# MAPE-CUN-Large-033.net
KiCad netlist of a schematic drawn in EAGLE
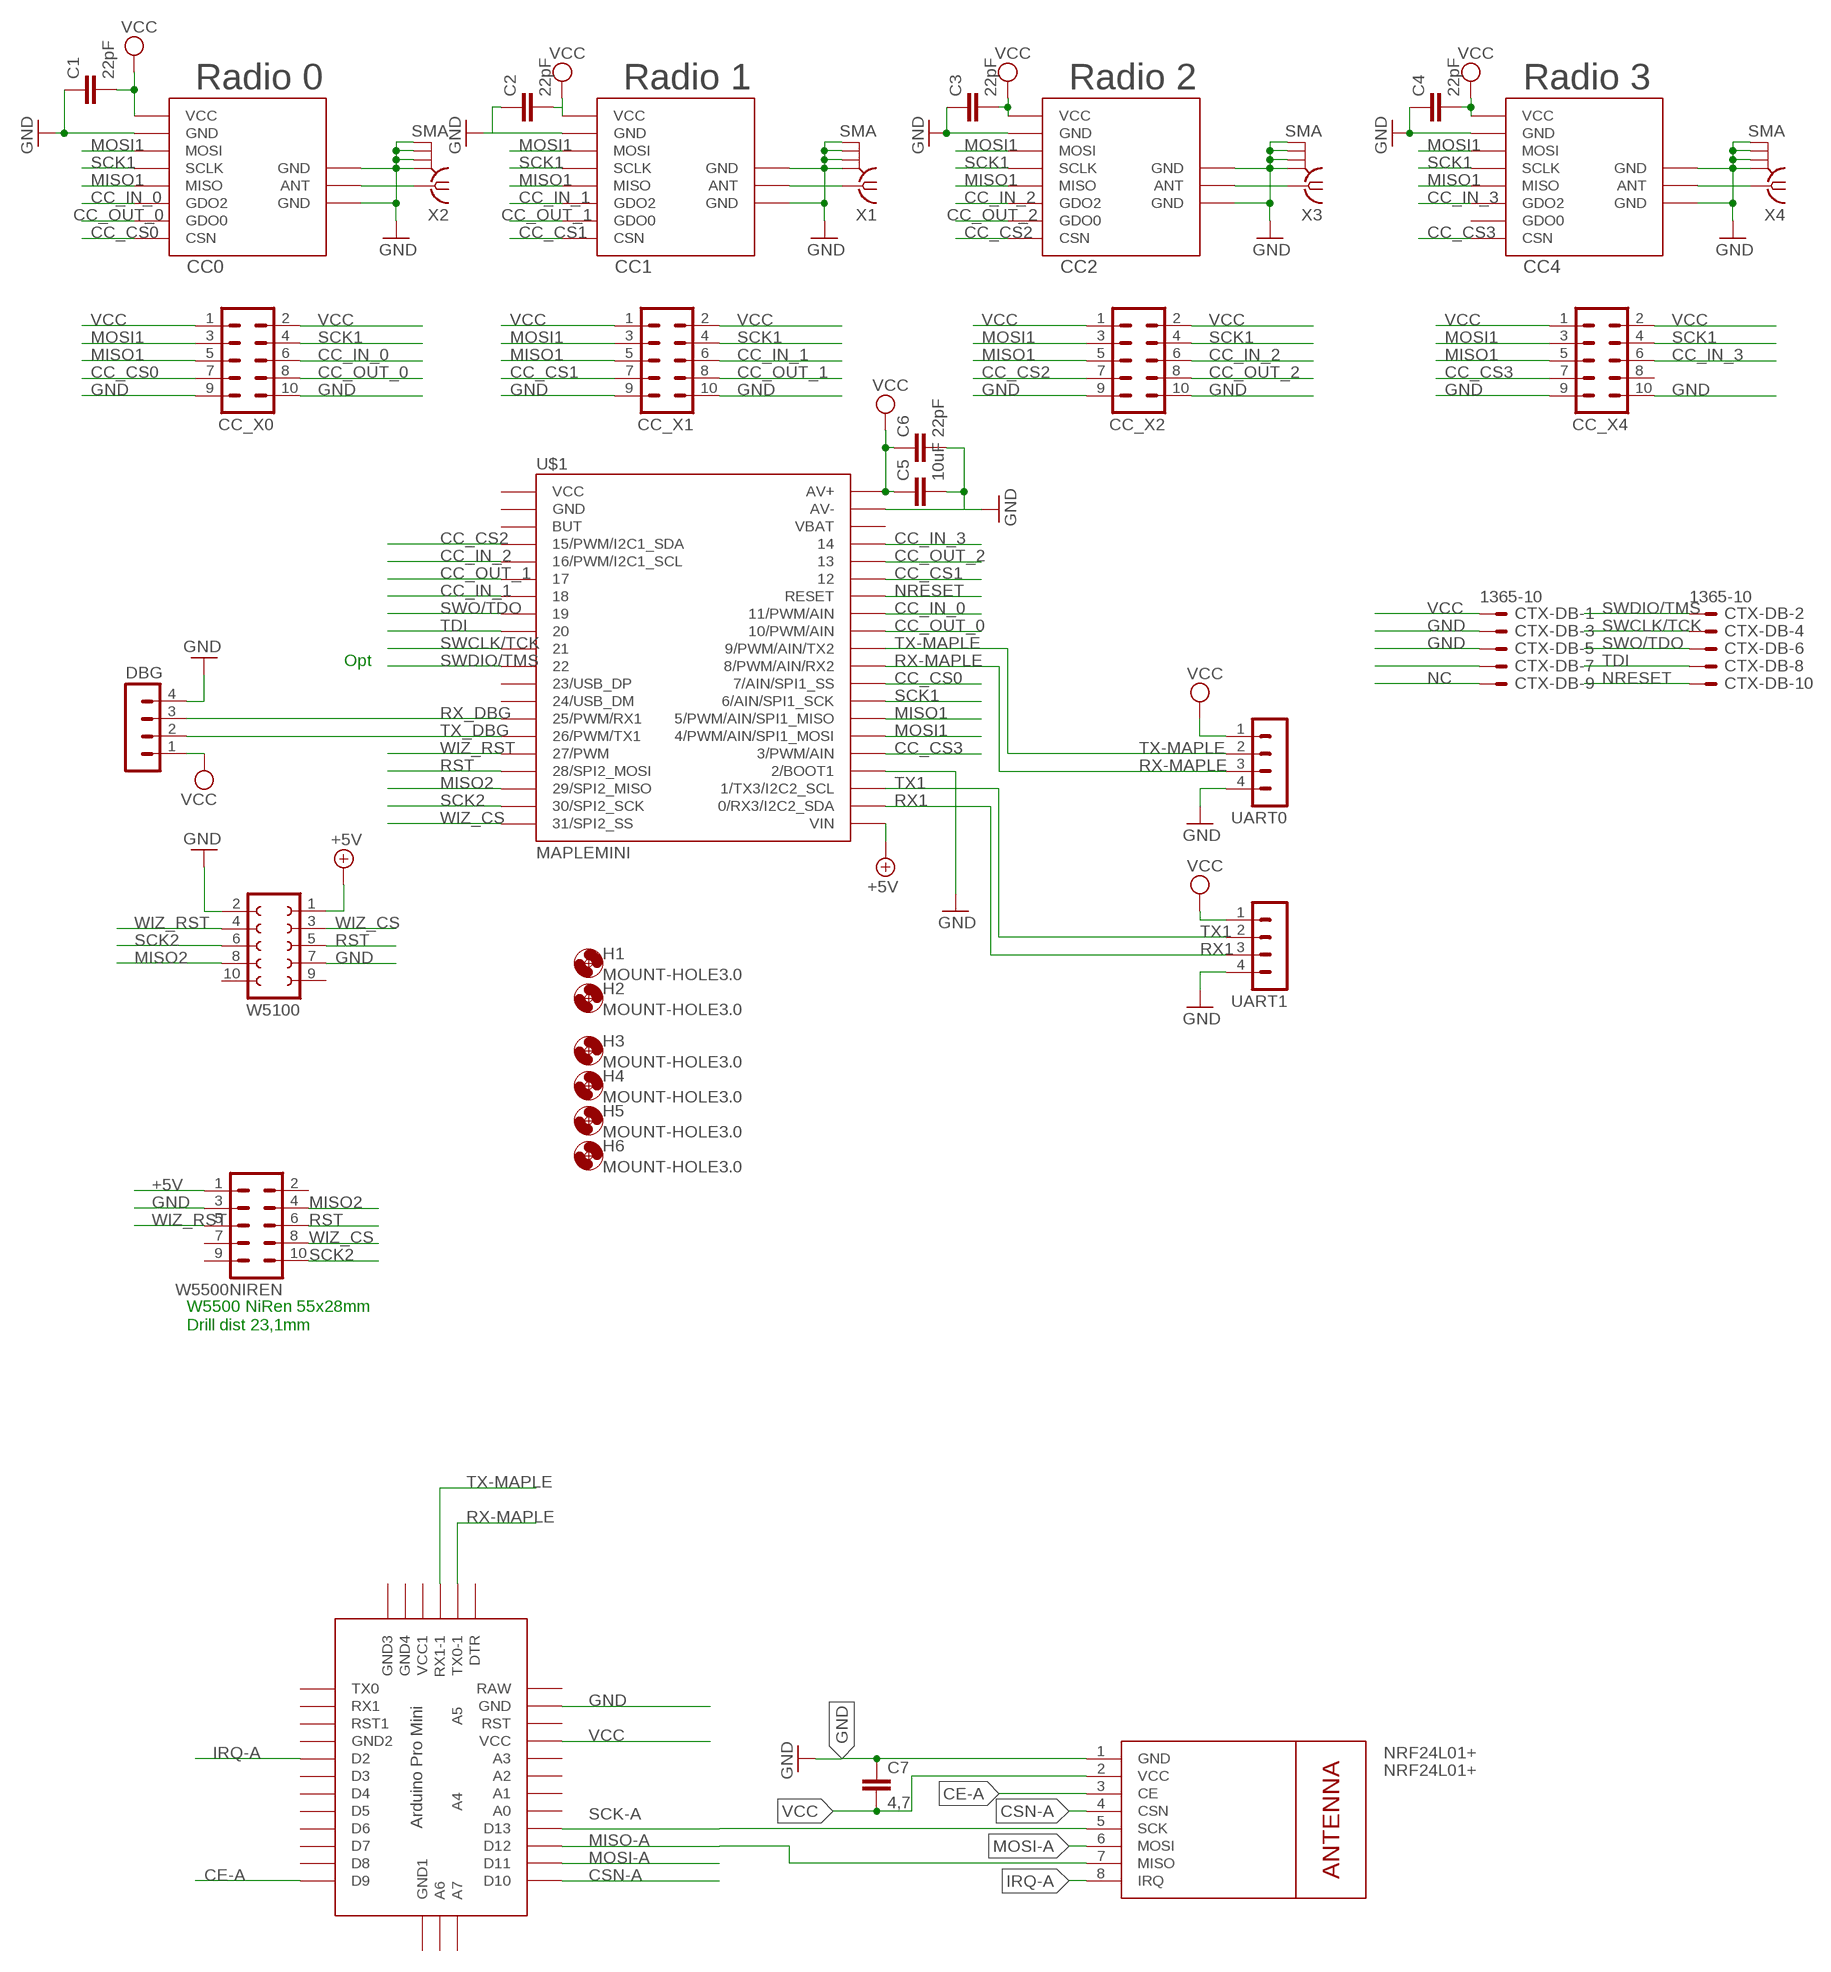
[diagram p0: schematic, sheet 1]

(export (version "E")
  (design (tool "Eeschema 10.0.6"))
  (components
    (comp (ref "C1")
      (value "22pF")
      (footprint "eagle-import:C0805")
      (libsource (lib "eagle-import") (part "C-EUC0805"))
    )
    (comp (ref "C2")
      (value "22pF")
      (footprint "eagle-import:C0805")
      (libsource (lib "eagle-import") (part "C-EUC0805"))
    )
    (comp (ref "C3")
      (value "22pF")
      (footprint "eagle-import:C0805")
      (libsource (lib "eagle-import") (part "C-EUC0805"))
    )
    (comp (ref "C4")
      (value "22pF")
      (footprint "eagle-import:C0805")
      (libsource (lib "eagle-import") (part "C-EUC0805"))
    )
    (comp (ref "C5")
      (value "10uF")
      (footprint "eagle-import:C1210")
      (libsource (lib "eagle-import") (part "C-EUC1210"))
    )
    (comp (ref "C6")
      (value "22pF")
      (footprint "eagle-import:C0805")
      (libsource (lib "eagle-import") (part "C-EUC0805"))
    )
    (comp (ref "C7")
      (value "4,7")
      (footprint "eagle-import:C1210")
      (libsource (lib "eagle-import") (part "C-EUC1210"))
    )
    (comp (ref "CC0")
      (value "CC1101_MODULE1SMD")
      (footprint "eagle-import:CC1101_MODULE1_SMD")
      (libsource (lib "eagle-import") (part "CC1101_MODULE1SMD"))
    )
    (comp (ref "CC1")
      (value "CC1101_MODULE1SMD")
      (footprint "eagle-import:CC1101_MODULE1_SMD")
      (libsource (lib "eagle-import") (part "CC1101_MODULE1SMD"))
    )
    (comp (ref "CC2")
      (value "CC1101_MODULE1SMD")
      (footprint "eagle-import:CC1101_MODULE1_SMD")
      (libsource (lib "eagle-import") (part "CC1101_MODULE1SMD"))
    )
    (comp (ref "CC4")
      (value "CC1101_MODULE1SMD")
      (footprint "eagle-import:CC1101_MODULE1_SMD")
      (libsource (lib "eagle-import") (part "CC1101_MODULE1SMD"))
    )
    (comp (ref "CC_X0")
      (value "MA05-2")
      (footprint "eagle-import:MA05-2")
      (libsource (lib "eagle-import") (part "MA05-2"))
    )
    (comp (ref "CC_X1")
      (value "MA05-2")
      (footprint "eagle-import:MA05-2")
      (libsource (lib "eagle-import") (part "MA05-2"))
    )
    (comp (ref "CC_X2")
      (value "MA05-2")
      (footprint "eagle-import:MA05-2")
      (libsource (lib "eagle-import") (part "MA05-2"))
    )
    (comp (ref "CC_X4")
      (value "MA05-2")
      (footprint "eagle-import:MA05-2")
      (libsource (lib "eagle-import") (part "MA05-2"))
    )
    (comp (ref "CTX-DB")
      (value "1365-10")
      (footprint "eagle-import:1365-10")
      (libsource (lib "eagle-import") (part "1365-10"))
    )
    (comp (ref "DBG")
      (value "MA04-1")
      (footprint "eagle-import:MA04-1")
      (libsource (lib "eagle-import") (part "MA04-1"))
    )
    (comp (ref "H1")
      (value "MOUNT-HOLE3.0")
      (footprint "eagle-import:3,0")
      (libsource (lib "eagle-import") (part "MOUNT-HOLE3.0"))
    )
    (comp (ref "H2")
      (value "MOUNT-HOLE3.0")
      (footprint "eagle-import:3,0")
      (libsource (lib "eagle-import") (part "MOUNT-HOLE3.0"))
    )
    (comp (ref "H3")
      (value "MOUNT-HOLE3.0")
      (footprint "eagle-import:3,0")
      (libsource (lib "eagle-import") (part "MOUNT-HOLE3.0"))
    )
    (comp (ref "H4")
      (value "MOUNT-HOLE3.0")
      (footprint "eagle-import:3,0")
      (libsource (lib "eagle-import") (part "MOUNT-HOLE3.0"))
    )
    (comp (ref "H5")
      (value "MOUNT-HOLE3.0")
      (footprint "eagle-import:3,0")
      (libsource (lib "eagle-import") (part "MOUNT-HOLE3.0"))
    )
    (comp (ref "H6")
      (value "MOUNT-HOLE3.0")
      (footprint "eagle-import:3,0")
      (libsource (lib "eagle-import") (part "MOUNT-HOLE3.0"))
    )
    (comp (ref "NRF24L01+")
      (value "NRF24L01+")
      (footprint "eagle-import:WIRELESS-NRF24L01")
      (libsource (lib "eagle-import") (part "WIRELESS-NRF24L01"))
    )
    (comp (ref "U$1")
      (value "MAPLEMINI")
      (footprint "eagle-import:20-DIP")
      (libsource (lib "eagle-import") (part "MAPLEMINI"))
    )
    (comp (ref "U$2")
      (value "ABK-PRO-MINI")
      (footprint "eagle-import:ABK-PRO-MINI")
      (libsource (lib "eagle-import") (part "ABK-PRO-MINI"))
    )
    (comp (ref "UART0")
      (value "MA04-1")
      (footprint "eagle-import:MA04-1")
      (libsource (lib "eagle-import") (part "MA04-1"))
    )
    (comp (ref "UART1")
      (value "MA04-1")
      (footprint "eagle-import:MA04-1")
      (libsource (lib "eagle-import") (part "MA04-1"))
    )
    (comp (ref "W5100")
      (value "FE05-2")
      (footprint "eagle-import:FE05-2")
      (libsource (lib "eagle-import") (part "FE05-2"))
    )
    (comp (ref "W5500NIREN")
      (value "MA05-2")
      (footprint "eagle-import:MA05-2")
      (libsource (lib "eagle-import") (part "MA05-2"))
    )
    (comp (ref "X1")
      (value "SMA")
      (footprint "eagle-import:SMA")
      (libsource (lib "eagle-import") (part "SMA"))
    )
    (comp (ref "X2")
      (value "SMA")
      (footprint "eagle-import:SMA")
      (libsource (lib "eagle-import") (part "SMA"))
    )
    (comp (ref "X3")
      (value "SMA")
      (footprint "eagle-import:SMA")
      (libsource (lib "eagle-import") (part "SMA"))
    )
    (comp (ref "X4")
      (value "SMA")
      (footprint "eagle-import:SMA")
      (libsource (lib "eagle-import") (part "SMA"))
    )
  )
  (nets
    (net (code "1") (name "+5V") (class "Default")
      (node (ref "U$1") (pin "21") (pinfunction "VIN_21") (pintype "bidirectional"))
      (node (ref "W5100") (pin "1") (pinfunction "1_1") (pintype "passive"))
      (node (ref "W5500NIREN") (pin "1") (pinfunction "1_1") (pintype "passive"))
    )
    (net (code "2") (name "/CC_CS0") (class "Default")
      (node (ref "CC0") (pin "CSN") (pinfunction "CSN_CSN") (pintype "bidirectional"))
      (node (ref "CC_X0") (pin "7") (pinfunction "7_7") (pintype "passive"))
      (node (ref "U$1") (pin "29") (pinfunction "7/AIN/SPI1_SS_29") (pintype "bidirectional"))
    )
    (net (code "3") (name "/CC_CS1") (class "Default")
      (node (ref "CC1") (pin "CSN") (pinfunction "CSN_CSN") (pintype "bidirectional"))
      (node (ref "CC_X1") (pin "7") (pinfunction "7_7") (pintype "passive"))
      (node (ref "U$1") (pin "35") (pinfunction "12_35") (pintype "bidirectional"))
    )
    (net (code "4") (name "/CC_CS2") (class "Default")
      (node (ref "CC2") (pin "CSN") (pinfunction "CSN_CSN") (pintype "bidirectional"))
      (node (ref "CC_X2") (pin "7") (pinfunction "7_7") (pintype "passive"))
      (node (ref "U$1") (pin "4") (pinfunction "15/PWM/I2C1_SDA_4") (pintype "bidirectional"))
    )
    (net (code "5") (name "/CC_CS3") (class "Default")
      (node (ref "CC4") (pin "CSN") (pinfunction "CSN_CSN") (pintype "bidirectional"))
      (node (ref "CC_X4") (pin "7") (pinfunction "7_7") (pintype "passive"))
      (node (ref "U$1") (pin "25") (pinfunction "3/PWM/AIN_25") (pintype "bidirectional"))
    )
    (net (code "6") (name "/CC_IN_0") (class "Default")
      (node (ref "CC0") (pin "GDO2") (pinfunction "GDO2_GDO2") (pintype "bidirectional"))
      (node (ref "CC_X0") (pin "6") (pinfunction "6_6") (pintype "passive"))
      (node (ref "U$1") (pin "33") (pinfunction "11/PWM/AIN_33") (pintype "bidirectional"))
    )
    (net (code "7") (name "/CC_IN_1") (class "Default")
      (node (ref "CC1") (pin "GDO2") (pinfunction "GDO2_GDO2") (pintype "bidirectional"))
      (node (ref "CC_X1") (pin "6") (pinfunction "6_6") (pintype "passive"))
      (node (ref "U$1") (pin "7") (pinfunction "18_7") (pintype "bidirectional"))
    )
    (net (code "8") (name "/CC_IN_2") (class "Default")
      (node (ref "CC2") (pin "GDO2") (pinfunction "GDO2_GDO2") (pintype "bidirectional"))
      (node (ref "CC_X2") (pin "6") (pinfunction "6_6") (pintype "passive"))
      (node (ref "U$1") (pin "5") (pinfunction "16/PWM/I2C1_SCL_5") (pintype "bidirectional"))
    )
    (net (code "9") (name "/CC_IN_3") (class "Default")
      (node (ref "CC4") (pin "GDO2") (pinfunction "GDO2_GDO2") (pintype "bidirectional"))
      (node (ref "CC_X4") (pin "6") (pinfunction "6_6") (pintype "passive"))
      (node (ref "U$1") (pin "37") (pinfunction "14_37") (pintype "bidirectional"))
    )
    (net (code "10") (name "/CC_OUT_0") (class "Default")
      (node (ref "CC0") (pin "GDO0") (pinfunction "GDO0_GDO0") (pintype "bidirectional"))
      (node (ref "CC_X0") (pin "8") (pinfunction "8_8") (pintype "passive"))
      (node (ref "U$1") (pin "32") (pinfunction "10/PWM/AIN_32") (pintype "bidirectional"))
    )
    (net (code "11") (name "/CC_OUT_1") (class "Default")
      (node (ref "CC1") (pin "GDO0") (pinfunction "GDO0_GDO0") (pintype "bidirectional"))
      (node (ref "CC_X1") (pin "8") (pinfunction "8_8") (pintype "passive"))
      (node (ref "U$1") (pin "6") (pinfunction "17_6") (pintype "bidirectional"))
    )
    (net (code "12") (name "/CC_OUT_2") (class "Default")
      (node (ref "CC2") (pin "GDO0") (pinfunction "GDO0_GDO0") (pintype "bidirectional"))
      (node (ref "CC_X2") (pin "8") (pinfunction "8_8") (pintype "passive"))
      (node (ref "U$1") (pin "36") (pinfunction "13_36") (pintype "bidirectional"))
    )
    (net (code "13") (name "/MISO-A") (class "Default")
      (node (ref "NRF24L01+") (pin "7") (pinfunction "MISO_7") (pintype "bidirectional"))
      (node (ref "U$2") (pin "D12") (pinfunction "D12_D12") (pintype "bidirectional"))
    )
    (net (code "14") (name "/MISO1") (class "Default")
      (node (ref "CC0") (pin "MISO") (pinfunction "MISO_MISO") (pintype "bidirectional"))
      (node (ref "CC1") (pin "MISO") (pinfunction "MISO_MISO") (pintype "bidirectional"))
      (node (ref "CC2") (pin "MISO") (pinfunction "MISO_MISO") (pintype "bidirectional"))
      (node (ref "CC4") (pin "MISO") (pinfunction "MISO_MISO") (pintype "bidirectional"))
      (node (ref "CC_X0") (pin "5") (pinfunction "5_5") (pintype "passive"))
      (node (ref "CC_X1") (pin "5") (pinfunction "5_5") (pintype "passive"))
      (node (ref "CC_X2") (pin "5") (pinfunction "5_5") (pintype "passive"))
      (node (ref "CC_X4") (pin "5") (pinfunction "5_5") (pintype "passive"))
      (node (ref "U$1") (pin "27") (pinfunction "5/PWM/AIN/SPI1_MISO_27") (pintype "bidirectional"))
    )
    (net (code "15") (name "/MISO2") (class "Default")
      (node (ref "U$1") (pin "18") (pinfunction "29/SPI2_MISO_18") (pintype "bidirectional"))
      (node (ref "W5100") (pin "8") (pinfunction "8_8") (pintype "passive"))
      (node (ref "W5500NIREN") (pin "4") (pinfunction "4_4") (pintype "passive"))
    )
    (net (code "16") (name "/MOSI1") (class "Default")
      (node (ref "CC0") (pin "MOSI") (pinfunction "MOSI_MOSI") (pintype "bidirectional"))
      (node (ref "CC1") (pin "MOSI") (pinfunction "MOSI_MOSI") (pintype "bidirectional"))
      (node (ref "CC2") (pin "MOSI") (pinfunction "MOSI_MOSI") (pintype "bidirectional"))
      (node (ref "CC4") (pin "MOSI") (pinfunction "MOSI_MOSI") (pintype "bidirectional"))
      (node (ref "CC_X0") (pin "3") (pinfunction "3_3") (pintype "passive"))
      (node (ref "CC_X1") (pin "3") (pinfunction "3_3") (pintype "passive"))
      (node (ref "CC_X2") (pin "3") (pinfunction "3_3") (pintype "passive"))
      (node (ref "CC_X4") (pin "3") (pinfunction "3_3") (pintype "passive"))
      (node (ref "U$1") (pin "26") (pinfunction "4/PWM/AIN/SPI1_MOSI_26") (pintype "bidirectional"))
    )
    (net (code "17") (name "/NC") (class "Default")
      (node (ref "CTX-DB") (pin "9") (pinfunction "S_9") (pintype "passive"))
    )
    (net (code "18") (name "/NRESET") (class "Default")
      (node (ref "CTX-DB") (pin "10") (pinfunction "S_10") (pintype "passive"))
      (node (ref "U$1") (pin "34") (pinfunction "RESET_34") (pintype "bidirectional"))
    )
    (net (code "19") (name "/RST") (class "Default")
      (node (ref "U$1") (pin "17") (pinfunction "28/SPI2_MOSI_17") (pintype "bidirectional"))
      (node (ref "W5100") (pin "5") (pinfunction "5_5") (pintype "passive"))
      (node (ref "W5500NIREN") (pin "6") (pinfunction "6_6") (pintype "passive"))
    )
    (net (code "20") (name "/RX-MAPLE") (class "Default")
      (node (ref "U$1") (pin "30") (pinfunction "8/PWM/AIN/RX2_30") (pintype "bidirectional"))
      (node (ref "U$2") (pin "TX0-1") (pinfunction "TX0-1_TX0-1") (pintype "bidirectional"))
      (node (ref "UART0") (pin "3") (pinfunction "3_3") (pintype "passive"))
    )
    (net (code "21") (name "/RX1") (class "Default")
      (node (ref "U$1") (pin "22") (pinfunction "0/RX3/I2C2_SDA_22") (pintype "bidirectional"))
      (node (ref "UART1") (pin "3") (pinfunction "3_3") (pintype "passive"))
    )
    (net (code "22") (name "/RX_DBG") (class "Default")
      (node (ref "DBG") (pin "3") (pinfunction "3_3") (pintype "passive"))
      (node (ref "U$1") (pin "14") (pinfunction "25/PWM/RX1_14") (pintype "bidirectional"))
    )
    (net (code "23") (name "/SCK-A") (class "Default")
      (node (ref "NRF24L01+") (pin "5") (pinfunction "SCK_5") (pintype "bidirectional"))
      (node (ref "U$2") (pin "D13") (pinfunction "D13_D13") (pintype "bidirectional"))
    )
    (net (code "24") (name "/SCK1") (class "Default")
      (node (ref "CC0") (pin "SCLK") (pinfunction "SCLK_SCLK") (pintype "bidirectional"))
      (node (ref "CC1") (pin "SCLK") (pinfunction "SCLK_SCLK") (pintype "bidirectional"))
      (node (ref "CC2") (pin "SCLK") (pinfunction "SCLK_SCLK") (pintype "bidirectional"))
      (node (ref "CC4") (pin "SCLK") (pinfunction "SCLK_SCLK") (pintype "bidirectional"))
      (node (ref "CC_X0") (pin "4") (pinfunction "4_4") (pintype "passive"))
      (node (ref "CC_X1") (pin "4") (pinfunction "4_4") (pintype "passive"))
      (node (ref "CC_X2") (pin "4") (pinfunction "4_4") (pintype "passive"))
      (node (ref "CC_X4") (pin "4") (pinfunction "4_4") (pintype "passive"))
      (node (ref "U$1") (pin "28") (pinfunction "6/AIN/SPI1_SCK_28") (pintype "bidirectional"))
    )
    (net (code "25") (name "/SCK2") (class "Default")
      (node (ref "U$1") (pin "19") (pinfunction "30/SPI2_SCK_19") (pintype "bidirectional"))
      (node (ref "W5100") (pin "6") (pinfunction "6_6") (pintype "passive"))
      (node (ref "W5500NIREN") (pin "10") (pinfunction "10_10") (pintype "passive"))
    )
    (net (code "26") (name "/SWCLK{slash}TCK") (class "Default")
      (node (ref "CTX-DB") (pin "4") (pinfunction "S_4") (pintype "passive"))
      (node (ref "U$1") (pin "10") (pinfunction "21_10") (pintype "bidirectional"))
    )
    (net (code "27") (name "/SWDIO{slash}TMS") (class "Default")
      (node (ref "CTX-DB") (pin "2") (pinfunction "S_2") (pintype "passive"))
      (node (ref "U$1") (pin "11") (pinfunction "22_11") (pintype "bidirectional"))
    )
    (net (code "28") (name "/SWO{slash}TDO") (class "Default")
      (node (ref "CTX-DB") (pin "6") (pinfunction "S_6") (pintype "passive"))
      (node (ref "U$1") (pin "8") (pinfunction "19_8") (pintype "bidirectional"))
    )
    (net (code "29") (name "/TDI") (class "Default")
      (node (ref "CTX-DB") (pin "8") (pinfunction "S_8") (pintype "passive"))
      (node (ref "U$1") (pin "9") (pinfunction "20_9") (pintype "bidirectional"))
    )
    (net (code "30") (name "/TX-MAPLE") (class "Default")
      (node (ref "U$1") (pin "31") (pinfunction "9/PWM/AIN/TX2_31") (pintype "bidirectional"))
      (node (ref "U$2") (pin "RX1-1") (pinfunction "RX1-1_RX1-1") (pintype "bidirectional"))
      (node (ref "UART0") (pin "2") (pinfunction "2_2") (pintype "passive"))
    )
    (net (code "31") (name "/TX1") (class "Default")
      (node (ref "U$1") (pin "23") (pinfunction "1/TX3/I2C2_SCL_23") (pintype "bidirectional"))
      (node (ref "UART1") (pin "2") (pinfunction "2_2") (pintype "passive"))
    )
    (net (code "32") (name "/TX_DBG") (class "Default")
      (node (ref "DBG") (pin "2") (pinfunction "2_2") (pintype "passive"))
      (node (ref "U$1") (pin "15") (pinfunction "26/PWM/TX1_15") (pintype "bidirectional"))
    )
    (net (code "33") (name "/WIZ_CS") (class "Default")
      (node (ref "U$1") (pin "20") (pinfunction "31/SPI2_SS_20") (pintype "bidirectional"))
      (node (ref "W5100") (pin "3") (pinfunction "3_3") (pintype "passive"))
      (node (ref "W5500NIREN") (pin "8") (pinfunction "8_8") (pintype "passive"))
    )
    (net (code "34") (name "/WIZ_RST") (class "Default")
      (node (ref "U$1") (pin "16") (pinfunction "27/PWM_16") (pintype "bidirectional"))
      (node (ref "W5100") (pin "4") (pinfunction "4_4") (pintype "passive"))
      (node (ref "W5500NIREN") (pin "5") (pinfunction "5_5") (pintype "passive"))
    )
    (net (code "35") (name "CE-A") (class "Default")
      (node (ref "NRF24L01+") (pin "3") (pinfunction "CE_3") (pintype "bidirectional"))
      (node (ref "U$2") (pin "D9") (pinfunction "D9_D9") (pintype "bidirectional"))
    )
    (net (code "36") (name "CSN-A") (class "Default")
      (node (ref "NRF24L01+") (pin "4") (pinfunction "CSN_4") (pintype "bidirectional"))
      (node (ref "U$2") (pin "D10") (pinfunction "D10_D10") (pintype "bidirectional"))
    )
    (net (code "37") (name "GND") (class "Default")
      (node (ref "C1") (pin "1") (pinfunction "1_1") (pintype "passive"))
      (node (ref "C2") (pin "1") (pinfunction "1_1") (pintype "passive"))
      (node (ref "C3") (pin "1") (pinfunction "1_1") (pintype "passive"))
      (node (ref "C4") (pin "1") (pinfunction "1_1") (pintype "passive"))
      (node (ref "C5") (pin "2") (pinfunction "2_2") (pintype "passive"))
      (node (ref "C6") (pin "2") (pinfunction "2_2") (pintype "passive"))
      (node (ref "C7") (pin "1") (pinfunction "1_1") (pintype "passive"))
      (node (ref "CC0") (pin "GND@0") (pinfunction "GND_GND@0") (pintype "power_in"))
      (node (ref "CC0") (pin "GND@1") (pinfunction "GND_GND@1") (pintype "power_in"))
      (node (ref "CC0") (pin "GND@2") (pinfunction "GND_GND@2") (pintype "power_in"))
      (node (ref "CC1") (pin "GND@0") (pinfunction "GND_GND@0") (pintype "power_in"))
      (node (ref "CC1") (pin "GND@1") (pinfunction "GND_GND@1") (pintype "power_in"))
      (node (ref "CC1") (pin "GND@2") (pinfunction "GND_GND@2") (pintype "power_in"))
      (node (ref "CC2") (pin "GND@0") (pinfunction "GND_GND@0") (pintype "power_in"))
      (node (ref "CC2") (pin "GND@1") (pinfunction "GND_GND@1") (pintype "power_in"))
      (node (ref "CC2") (pin "GND@2") (pinfunction "GND_GND@2") (pintype "power_in"))
      (node (ref "CC4") (pin "GND@0") (pinfunction "GND_GND@0") (pintype "power_in"))
      (node (ref "CC4") (pin "GND@1") (pinfunction "GND_GND@1") (pintype "power_in"))
      (node (ref "CC4") (pin "GND@2") (pinfunction "GND_GND@2") (pintype "power_in"))
      (node (ref "CC_X0") (pin "10") (pinfunction "10_10") (pintype "passive"))
      (node (ref "CC_X0") (pin "9") (pinfunction "9_9") (pintype "passive"))
      (node (ref "CC_X1") (pin "10") (pinfunction "10_10") (pintype "passive"))
      (node (ref "CC_X1") (pin "9") (pinfunction "9_9") (pintype "passive"))
      (node (ref "CC_X2") (pin "10") (pinfunction "10_10") (pintype "passive"))
      (node (ref "CC_X2") (pin "9") (pinfunction "9_9") (pintype "passive"))
      (node (ref "CC_X4") (pin "10") (pinfunction "10_10") (pintype "passive"))
      (node (ref "CC_X4") (pin "9") (pinfunction "9_9") (pintype "passive"))
      (node (ref "CTX-DB") (pin "3") (pinfunction "S_3") (pintype "passive"))
      (node (ref "CTX-DB") (pin "5") (pinfunction "S_5") (pintype "passive"))
      (node (ref "DBG") (pin "4") (pinfunction "4_4") (pintype "passive"))
      (node (ref "NRF24L01+") (pin "1") (pinfunction "GND_1") (pintype "power_in"))
      (node (ref "U$1") (pin "24") (pinfunction "2/BOOT1_24") (pintype "bidirectional"))
      (node (ref "U$1") (pin "39") (pinfunction "AV-_39") (pintype "bidirectional"))
      (node (ref "U$2") (pin "GND") (pinfunction "GND_GND") (pintype "bidirectional"))
      (node (ref "UART0") (pin "4") (pinfunction "4_4") (pintype "passive"))
      (node (ref "UART1") (pin "4") (pinfunction "4_4") (pintype "passive"))
      (node (ref "W5100") (pin "2") (pinfunction "2_2") (pintype "passive"))
      (node (ref "W5100") (pin "7") (pinfunction "7_7") (pintype "passive"))
      (node (ref "W5500NIREN") (pin "3") (pinfunction "3_3") (pintype "passive"))
      (node (ref "X1") (pin "GND@1") (pinfunction "2_GND@1") (pintype "passive"))
      (node (ref "X1") (pin "GND@2") (pinfunction "3_GND@2") (pintype "passive"))
      (node (ref "X1") (pin "GND@3") (pinfunction "4_GND@3") (pintype "passive"))
      (node (ref "X1") (pin "GND@4") (pinfunction "5_GND@4") (pintype "passive"))
      (node (ref "X2") (pin "GND@1") (pinfunction "2_GND@1") (pintype "passive"))
      (node (ref "X2") (pin "GND@2") (pinfunction "3_GND@2") (pintype "passive"))
      (node (ref "X2") (pin "GND@3") (pinfunction "4_GND@3") (pintype "passive"))
      (node (ref "X2") (pin "GND@4") (pinfunction "5_GND@4") (pintype "passive"))
      (node (ref "X3") (pin "GND@1") (pinfunction "2_GND@1") (pintype "passive"))
      (node (ref "X3") (pin "GND@2") (pinfunction "3_GND@2") (pintype "passive"))
      (node (ref "X3") (pin "GND@3") (pinfunction "4_GND@3") (pintype "passive"))
      (node (ref "X3") (pin "GND@4") (pinfunction "5_GND@4") (pintype "passive"))
      (node (ref "X4") (pin "GND@1") (pinfunction "2_GND@1") (pintype "passive"))
      (node (ref "X4") (pin "GND@2") (pinfunction "3_GND@2") (pintype "passive"))
      (node (ref "X4") (pin "GND@3") (pinfunction "4_GND@3") (pintype "passive"))
      (node (ref "X4") (pin "GND@4") (pinfunction "5_GND@4") (pintype "passive"))
    )
    (net (code "38") (name "IRQ-A") (class "Default")
      (node (ref "NRF24L01+") (pin "8") (pinfunction "IRQ_8") (pintype "bidirectional"))
      (node (ref "U$2") (pin "D2") (pinfunction "D2_D2") (pintype "bidirectional"))
    )
    (net (code "39") (name "MOSI-A") (class "Default")
      (node (ref "NRF24L01+") (pin "6") (pinfunction "MOSI_6") (pintype "bidirectional"))
      (node (ref "U$2") (pin "D11") (pinfunction "D11_D11") (pintype "bidirectional"))
    )
    (net (code "40") (name "Net-(CC0-PadANT)") (class "Default")
      (node (ref "CC0") (pin "ANT") (pinfunction "ANT_ANT") (pintype "output"))
      (node (ref "X2") (pin "1") (pinfunction "1_1") (pintype "passive"))
    )
    (net (code "41") (name "Net-(CC1-PadANT)") (class "Default")
      (node (ref "CC1") (pin "ANT") (pinfunction "ANT_ANT") (pintype "output"))
      (node (ref "X1") (pin "1") (pinfunction "1_1") (pintype "passive"))
    )
    (net (code "42") (name "Net-(CC2-PadANT)") (class "Default")
      (node (ref "CC2") (pin "ANT") (pinfunction "ANT_ANT") (pintype "output"))
      (node (ref "X3") (pin "1") (pinfunction "1_1") (pintype "passive"))
    )
    (net (code "43") (name "Net-(CC4-PadANT)") (class "Default")
      (node (ref "CC4") (pin "ANT") (pinfunction "ANT_ANT") (pintype "output"))
      (node (ref "X4") (pin "1") (pinfunction "1_1") (pintype "passive"))
    )
    (net (code "44") (name "VCC") (class "Default")
      (node (ref "C1") (pin "2") (pinfunction "2_2") (pintype "passive"))
      (node (ref "C2") (pin "2") (pinfunction "2_2") (pintype "passive"))
      (node (ref "C3") (pin "2") (pinfunction "2_2") (pintype "passive"))
      (node (ref "C4") (pin "2") (pinfunction "2_2") (pintype "passive"))
      (node (ref "C5") (pin "1") (pinfunction "1_1") (pintype "passive"))
      (node (ref "C6") (pin "1") (pinfunction "1_1") (pintype "passive"))
      (node (ref "C7") (pin "2") (pinfunction "2_2") (pintype "passive"))
      (node (ref "CC0") (pin "VCC") (pinfunction "VCC_VCC") (pintype "power_in"))
      (node (ref "CC1") (pin "VCC") (pinfunction "VCC_VCC") (pintype "power_in"))
      (node (ref "CC2") (pin "VCC") (pinfunction "VCC_VCC") (pintype "power_in"))
      (node (ref "CC4") (pin "VCC") (pinfunction "VCC_VCC") (pintype "power_in"))
      (node (ref "CC_X0") (pin "1") (pinfunction "1_1") (pintype "passive"))
      (node (ref "CC_X0") (pin "2") (pinfunction "2_2") (pintype "passive"))
      (node (ref "CC_X1") (pin "1") (pinfunction "1_1") (pintype "passive"))
      (node (ref "CC_X1") (pin "2") (pinfunction "2_2") (pintype "passive"))
      (node (ref "CC_X2") (pin "1") (pinfunction "1_1") (pintype "passive"))
      (node (ref "CC_X2") (pin "2") (pinfunction "2_2") (pintype "passive"))
      (node (ref "CC_X4") (pin "1") (pinfunction "1_1") (pintype "passive"))
      (node (ref "CC_X4") (pin "2") (pinfunction "2_2") (pintype "passive"))
      (node (ref "CTX-DB") (pin "1") (pinfunction "S_1") (pintype "passive"))
      (node (ref "DBG") (pin "1") (pinfunction "1_1") (pintype "passive"))
      (node (ref "NRF24L01+") (pin "2") (pinfunction "VCC_2") (pintype "power_in"))
      (node (ref "U$1") (pin "40") (pinfunction "AV+_40") (pintype "bidirectional"))
      (node (ref "U$2") (pin "VCC") (pinfunction "VCC_VCC") (pintype "bidirectional"))
      (node (ref "UART0") (pin "1") (pinfunction "1_1") (pintype "passive"))
      (node (ref "UART1") (pin "1") (pinfunction "1_1") (pintype "passive"))
    )
    (net (code "45") (name "unconnected-(CC4-PadGDO0)") (class "Default")
      (node (ref "CC4") (pin "GDO0") (pinfunction "GDO0_GDO0") (pintype "bidirectional"))
    )
    (net (code "46") (name "unconnected-(CC_X4-Pad8)") (class "Default")
      (node (ref "CC_X4") (pin "8") (pinfunction "8_8") (pintype "passive"))
    )
    (net (code "47") (name "unconnected-(CTX-DBH-S-Pad7)") (class "Default")
      (node (ref "CTX-DB") (pin "7") (pinfunction "S_7") (pintype "passive"))
    )
    (net (code "48") (name "unconnected-(U$1-23{slash}USB_DP-Pad12)") (class "Default")
      (node (ref "U$1") (pin "12") (pinfunction "23/USB_DP_12") (pintype "bidirectional"))
    )
    (net (code "49") (name "unconnected-(U$1-24{slash}USB_DM-Pad13)") (class "Default")
      (node (ref "U$1") (pin "13") (pinfunction "24/USB_DM_13") (pintype "bidirectional"))
    )
    (net (code "50") (name "unconnected-(U$1-BUT-Pad3)") (class "Default")
      (node (ref "U$1") (pin "3") (pinfunction "BUT_3") (pintype "bidirectional"))
    )
    (net (code "51") (name "unconnected-(U$1-GND-Pad2)") (class "Default")
      (node (ref "U$1") (pin "2") (pinfunction "GND_2") (pintype "bidirectional"))
    )
    (net (code "52") (name "unconnected-(U$1-VBAT-Pad38)") (class "Default")
      (node (ref "U$1") (pin "38") (pinfunction "VBAT_38") (pintype "bidirectional"))
    )
    (net (code "53") (name "unconnected-(U$1-VCC-Pad1)") (class "Default")
      (node (ref "U$1") (pin "1") (pinfunction "VCC_1") (pintype "bidirectional"))
    )
    (net (code "54") (name "unconnected-(U$2-GND1-PadGND4)") (class "Default")
      (node (ref "U$2") (pin "GND4") (pinfunction "GND1_GND4") (pintype "bidirectional"))
    )
    (net (code "55") (name "unconnected-(U$2-GND2-PadGND1)") (class "Default")
      (node (ref "U$2") (pin "GND1") (pinfunction "GND2_GND1") (pintype "bidirectional"))
    )
    (net (code "56") (name "unconnected-(U$2-GND3-PadGND2)") (class "Default")
      (node (ref "U$2") (pin "GND2") (pinfunction "GND3_GND2") (pintype "bidirectional"))
    )
    (net (code "57") (name "unconnected-(U$2-GND4-PadGND3)") (class "Default")
      (node (ref "U$2") (pin "GND3") (pinfunction "GND4_GND3") (pintype "bidirectional"))
    )
    (net (code "58") (name "unconnected-(U$2-PadA0)") (class "Default")
      (node (ref "U$2") (pin "A0") (pinfunction "A0_A0") (pintype "bidirectional"))
    )
    (net (code "59") (name "unconnected-(U$2-PadA1)") (class "Default")
      (node (ref "U$2") (pin "A1") (pinfunction "A1_A1") (pintype "bidirectional"))
    )
    (net (code "60") (name "unconnected-(U$2-PadA2)") (class "Default")
      (node (ref "U$2") (pin "A2") (pinfunction "A2_A2") (pintype "bidirectional"))
    )
    (net (code "61") (name "unconnected-(U$2-PadA3)") (class "Default")
      (node (ref "U$2") (pin "A3") (pinfunction "A3_A3") (pintype "bidirectional"))
    )
    (net (code "62") (name "unconnected-(U$2-PadA4)") (class "Default")
      (node (ref "U$2") (pin "A4") (pinfunction "A4_A4") (pintype "bidirectional"))
    )
    (net (code "63") (name "unconnected-(U$2-PadA5)") (class "Default")
      (node (ref "U$2") (pin "A5") (pinfunction "A5_A5") (pintype "bidirectional"))
    )
    (net (code "64") (name "unconnected-(U$2-PadA6)") (class "Default")
      (node (ref "U$2") (pin "A6") (pinfunction "A6_A6") (pintype "bidirectional"))
    )
    (net (code "65") (name "unconnected-(U$2-PadA7)") (class "Default")
      (node (ref "U$2") (pin "A7") (pinfunction "A7_A7") (pintype "bidirectional"))
    )
    (net (code "66") (name "unconnected-(U$2-PadD3)") (class "Default")
      (node (ref "U$2") (pin "D3") (pinfunction "D3_D3") (pintype "bidirectional"))
    )
    (net (code "67") (name "unconnected-(U$2-PadD4)") (class "Default")
      (node (ref "U$2") (pin "D4") (pinfunction "D4_D4") (pintype "bidirectional"))
    )
    (net (code "68") (name "unconnected-(U$2-PadD5)") (class "Default")
      (node (ref "U$2") (pin "D5") (pinfunction "D5_D5") (pintype "bidirectional"))
    )
    (net (code "69") (name "unconnected-(U$2-PadD6)") (class "Default")
      (node (ref "U$2") (pin "D6") (pinfunction "D6_D6") (pintype "bidirectional"))
    )
    (net (code "70") (name "unconnected-(U$2-PadD7)") (class "Default")
      (node (ref "U$2") (pin "D7") (pinfunction "D7_D7") (pintype "bidirectional"))
    )
    (net (code "71") (name "unconnected-(U$2-PadD8)") (class "Default")
      (node (ref "U$2") (pin "D8") (pinfunction "D8_D8") (pintype "bidirectional"))
    )
    (net (code "72") (name "unconnected-(U$2-PadDTR)") (class "Default")
      (node (ref "U$2") (pin "DTR") (pinfunction "DTR_DTR") (pintype "bidirectional"))
    )
    (net (code "73") (name "unconnected-(U$2-PadRAW)") (class "Default")
      (node (ref "U$2") (pin "RAW") (pinfunction "RAW_RAW") (pintype "bidirectional"))
    )
    (net (code "74") (name "unconnected-(U$2-PadRST)") (class "Default")
      (node (ref "U$2") (pin "RST") (pinfunction "RST_RST") (pintype "bidirectional"))
    )
    (net (code "75") (name "unconnected-(U$2-PadRST1)") (class "Default")
      (node (ref "U$2") (pin "RST1") (pinfunction "RST1_RST1") (pintype "bidirectional"))
    )
    (net (code "76") (name "unconnected-(U$2-PadRX1)") (class "Default")
      (node (ref "U$2") (pin "RX1") (pinfunction "RX1_RX1") (pintype "bidirectional"))
    )
    (net (code "77") (name "unconnected-(U$2-PadTX0)") (class "Default")
      (node (ref "U$2") (pin "TX0") (pinfunction "TX0_TX0") (pintype "bidirectional"))
    )
    (net (code "78") (name "unconnected-(U$2-PadVCC1)") (class "Default")
      (node (ref "U$2") (pin "VCC1") (pinfunction "VCC1_VCC1") (pintype "bidirectional"))
    )
    (net (code "79") (name "unconnected-(W5100-Pad9)") (class "Default")
      (node (ref "W5100") (pin "9") (pinfunction "9_9") (pintype "passive"))
    )
    (net (code "80") (name "unconnected-(W5100-Pad10)") (class "Default")
      (node (ref "W5100") (pin "10") (pinfunction "10_10") (pintype "passive"))
    )
    (net (code "81") (name "unconnected-(W5500NIREN-Pad2)") (class "Default")
      (node (ref "W5500NIREN") (pin "2") (pinfunction "2_2") (pintype "passive"))
    )
    (net (code "82") (name "unconnected-(W5500NIREN-Pad7)") (class "Default")
      (node (ref "W5500NIREN") (pin "7") (pinfunction "7_7") (pintype "passive"))
    )
    (net (code "83") (name "unconnected-(W5500NIREN-Pad9)") (class "Default")
      (node (ref "W5500NIREN") (pin "9") (pinfunction "9_9") (pintype "passive"))
    )
  )
)
